# Connectors.net
KiCad netlist of a schematic drawn in Altium Designer
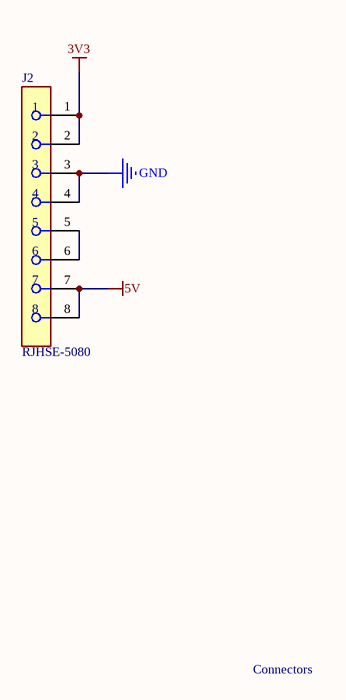
[diagram p0: Connectors.SchDoc]

(export (version "E")
  (design (tool "Eeschema 10.0.6"))
  (components
    (comp (ref "J2")
      (value "RJHSE-5080")
      (footprint "FP-RJHSE-5080-MFG")
      (description "CONN MOD JACK 8P8C R/A UNSHLD")
      (fields
        (field (name "OCTOPART") "https://octopart.com/rjhse-5080-amphenol-45060")
        (field (name "MANUFACTURER") "Amphenol")
      )
      (libsource (lib "Altium Content Vault") (part "b0a0b555dd3abf3683e7c330df25cc4"))
    )
  )
  (nets
    (net (code "1") (name "3V3") (class "Default")
      (node (ref "J2") (pin "1") (pinfunction "1_1") (pintype "passive"))
      (node (ref "J2") (pin "2") (pinfunction "2_2") (pintype "passive"))
    )
    (net (code "2") (name "5V") (class "Default")
      (node (ref "J2") (pin "7") (pinfunction "7_7") (pintype "passive"))
      (node (ref "J2") (pin "8") (pinfunction "8_8") (pintype "passive"))
    )
    (net (code "3") (name "GND") (class "Default")
      (node (ref "J2") (pin "3") (pinfunction "3_3") (pintype "passive"))
      (node (ref "J2") (pin "4") (pinfunction "4_4") (pintype "passive"))
    )
    (net (code "4") (name "Net-(J2-Pad5)") (class "Default")
      (node (ref "J2") (pin "5") (pinfunction "5_5") (pintype "passive"))
      (node (ref "J2") (pin "6") (pinfunction "6_6") (pintype "passive"))
    )
  )
)
